# Mabee_Serial_WiFi_V1_1.net
KiCad netlist of a schematic drawn in EAGLE
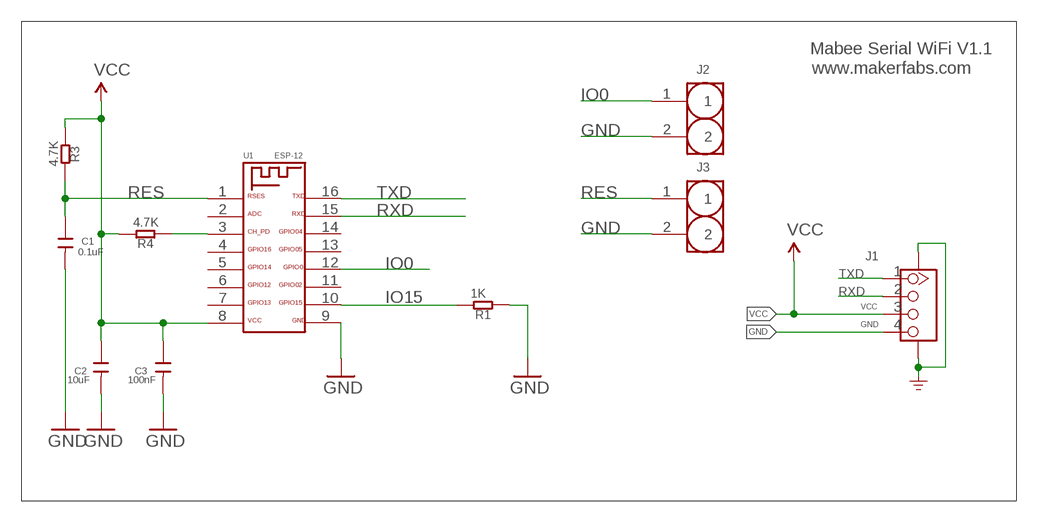
[diagram p0: schematic, sheet 1]

(export (version "E")
  (design (tool "Eeschema 10.0.6"))
  (components
    (comp (ref "C1")
      (value "0.1uF")
      (footprint "eagle-import:C0603")
      (libsource (lib "eagle-import") (part "C-0603"))
    )
    (comp (ref "C2")
      (value "10uF")
      (footprint "eagle-import:C0603")
      (libsource (lib "eagle-import") (part "C-0603"))
    )
    (comp (ref "C3")
      (value "100nF")
      (footprint "eagle-import:C0603")
      (libsource (lib "eagle-import") (part "C-0603"))
    )
    (comp (ref "J1")
      (value "GROVE-CONNECTOR-SMD'90D'")
      (footprint "eagle-import:HW4-SMD-2.0-90D")
      (libsource (lib "eagle-import") (part "GROVE-CONNECTOR-SMD'90D'"))
    )
    (comp (ref "J2")
      (value "HEADER-2P-65/35MIL")
      (footprint "eagle-import:2P-2.54-65_35MIL")
      (libsource (lib "eagle-import") (part "HEADER-2P-65/35MIL"))
    )
    (comp (ref "J3")
      (value "HEADER-2P-65/35MIL")
      (footprint "eagle-import:2P-2.54-65_35MIL")
      (libsource (lib "eagle-import") (part "HEADER-2P-65/35MIL"))
    )
    (comp (ref "R1")
      (value "1K")
      (footprint "eagle-import:0603")
      (libsource (lib "eagle-import") (part "R-0603"))
    )
    (comp (ref "R3")
      (value "4.7K")
      (footprint "eagle-import:0603")
      (libsource (lib "eagle-import") (part "R-0603"))
    )
    (comp (ref "R4")
      (value "4.7K")
      (footprint "eagle-import:0603")
      (libsource (lib "eagle-import") (part "R-0603"))
    )
    (comp (ref "U1")
      (value "ESP-12")
      (footprint "eagle-import:ESP-12")
      (libsource (lib "eagle-import") (part "ESP-12"))
    )
  )
  (nets
    (net (code "1") (name "/IO0") (class "Default")
      (node (ref "J2") (pin "1") (pinfunction "1_1") (pintype "bidirectional"))
      (node (ref "U1") (pin "12") (pinfunction "12_12") (pintype "bidirectional"))
    )
    (net (code "2") (name "/IO15") (class "Default")
      (node (ref "R1") (pin "2") (pinfunction "2_2") (pintype "passive"))
      (node (ref "U1") (pin "10") (pinfunction "10_10") (pintype "bidirectional"))
    )
    (net (code "3") (name "/RES") (class "Default")
      (node (ref "C1") (pin "1") (pinfunction "1_1") (pintype "passive"))
      (node (ref "J3") (pin "1") (pinfunction "1_1") (pintype "bidirectional"))
      (node (ref "R3") (pin "2") (pinfunction "2_2") (pintype "passive"))
      (node (ref "U1") (pin "1") (pinfunction "1_1") (pintype "bidirectional"))
    )
    (net (code "4") (name "/RXD") (class "Default")
      (node (ref "J1") (pin "2") (pinfunction "2_2") (pintype "bidirectional"))
      (node (ref "U1") (pin "15") (pinfunction "15_15") (pintype "bidirectional"))
    )
    (net (code "5") (name "/TXD") (class "Default")
      (node (ref "J1") (pin "1") (pinfunction "1_1") (pintype "bidirectional"))
      (node (ref "U1") (pin "16") (pinfunction "16_16") (pintype "bidirectional"))
    )
    (net (code "6") (name "GND") (class "Default")
      (node (ref "C1") (pin "2") (pinfunction "2_2") (pintype "passive"))
      (node (ref "C2") (pin "2") (pinfunction "2_2") (pintype "passive"))
      (node (ref "C3") (pin "2") (pinfunction "2_2") (pintype "passive"))
      (node (ref "J1") (pin "4") (pinfunction "4_4") (pintype "bidirectional"))
      (node (ref "J1") (pin "SS1") (pinfunction "SS1_SS1") (pintype "bidirectional"))
      (node (ref "J1") (pin "SS2") (pinfunction "SS2_SS2") (pintype "bidirectional"))
      (node (ref "J2") (pin "2") (pinfunction "2_2") (pintype "bidirectional"))
      (node (ref "J3") (pin "2") (pinfunction "2_2") (pintype "bidirectional"))
      (node (ref "R1") (pin "1") (pinfunction "1_1") (pintype "passive"))
      (node (ref "U1") (pin "9") (pinfunction "9_9") (pintype "bidirectional"))
    )
    (net (code "7") (name "Net-(R4-Pad1)") (class "Default")
      (node (ref "R4") (pin "1") (pinfunction "1_1") (pintype "passive"))
      (node (ref "U1") (pin "3") (pinfunction "3_3") (pintype "bidirectional"))
    )
    (net (code "8") (name "VCC") (class "Default")
      (node (ref "C2") (pin "1") (pinfunction "1_1") (pintype "passive"))
      (node (ref "C3") (pin "1") (pinfunction "1_1") (pintype "passive"))
      (node (ref "J1") (pin "3") (pinfunction "3_3") (pintype "bidirectional"))
      (node (ref "R3") (pin "1") (pinfunction "1_1") (pintype "passive"))
      (node (ref "R4") (pin "2") (pinfunction "2_2") (pintype "passive"))
      (node (ref "U1") (pin "8") (pinfunction "8_8") (pintype "bidirectional"))
    )
    (net (code "9") (name "unconnected-(U1-Pad2)") (class "Default")
      (node (ref "U1") (pin "2") (pinfunction "2_2") (pintype "bidirectional"))
    )
    (net (code "10") (name "unconnected-(U1-Pad4)") (class "Default")
      (node (ref "U1") (pin "4") (pinfunction "4_4") (pintype "bidirectional"))
    )
    (net (code "11") (name "unconnected-(U1-Pad5)") (class "Default")
      (node (ref "U1") (pin "5") (pinfunction "5_5") (pintype "bidirectional"))
    )
    (net (code "12") (name "unconnected-(U1-Pad6)") (class "Default")
      (node (ref "U1") (pin "6") (pinfunction "6_6") (pintype "bidirectional"))
    )
    (net (code "13") (name "unconnected-(U1-Pad7)") (class "Default")
      (node (ref "U1") (pin "7") (pinfunction "7_7") (pintype "bidirectional"))
    )
    (net (code "14") (name "unconnected-(U1-Pad11)") (class "Default")
      (node (ref "U1") (pin "11") (pinfunction "11_11") (pintype "bidirectional"))
    )
    (net (code "15") (name "unconnected-(U1-Pad13)") (class "Default")
      (node (ref "U1") (pin "13") (pinfunction "13_13") (pintype "bidirectional"))
    )
    (net (code "16") (name "unconnected-(U1-Pad14)") (class "Default")
      (node (ref "U1") (pin "14") (pinfunction "14_14") (pintype "bidirectional"))
    )
  )
)
